# MainBoard_Box.net
KiCad netlist of a schematic drawn in Altium Designer
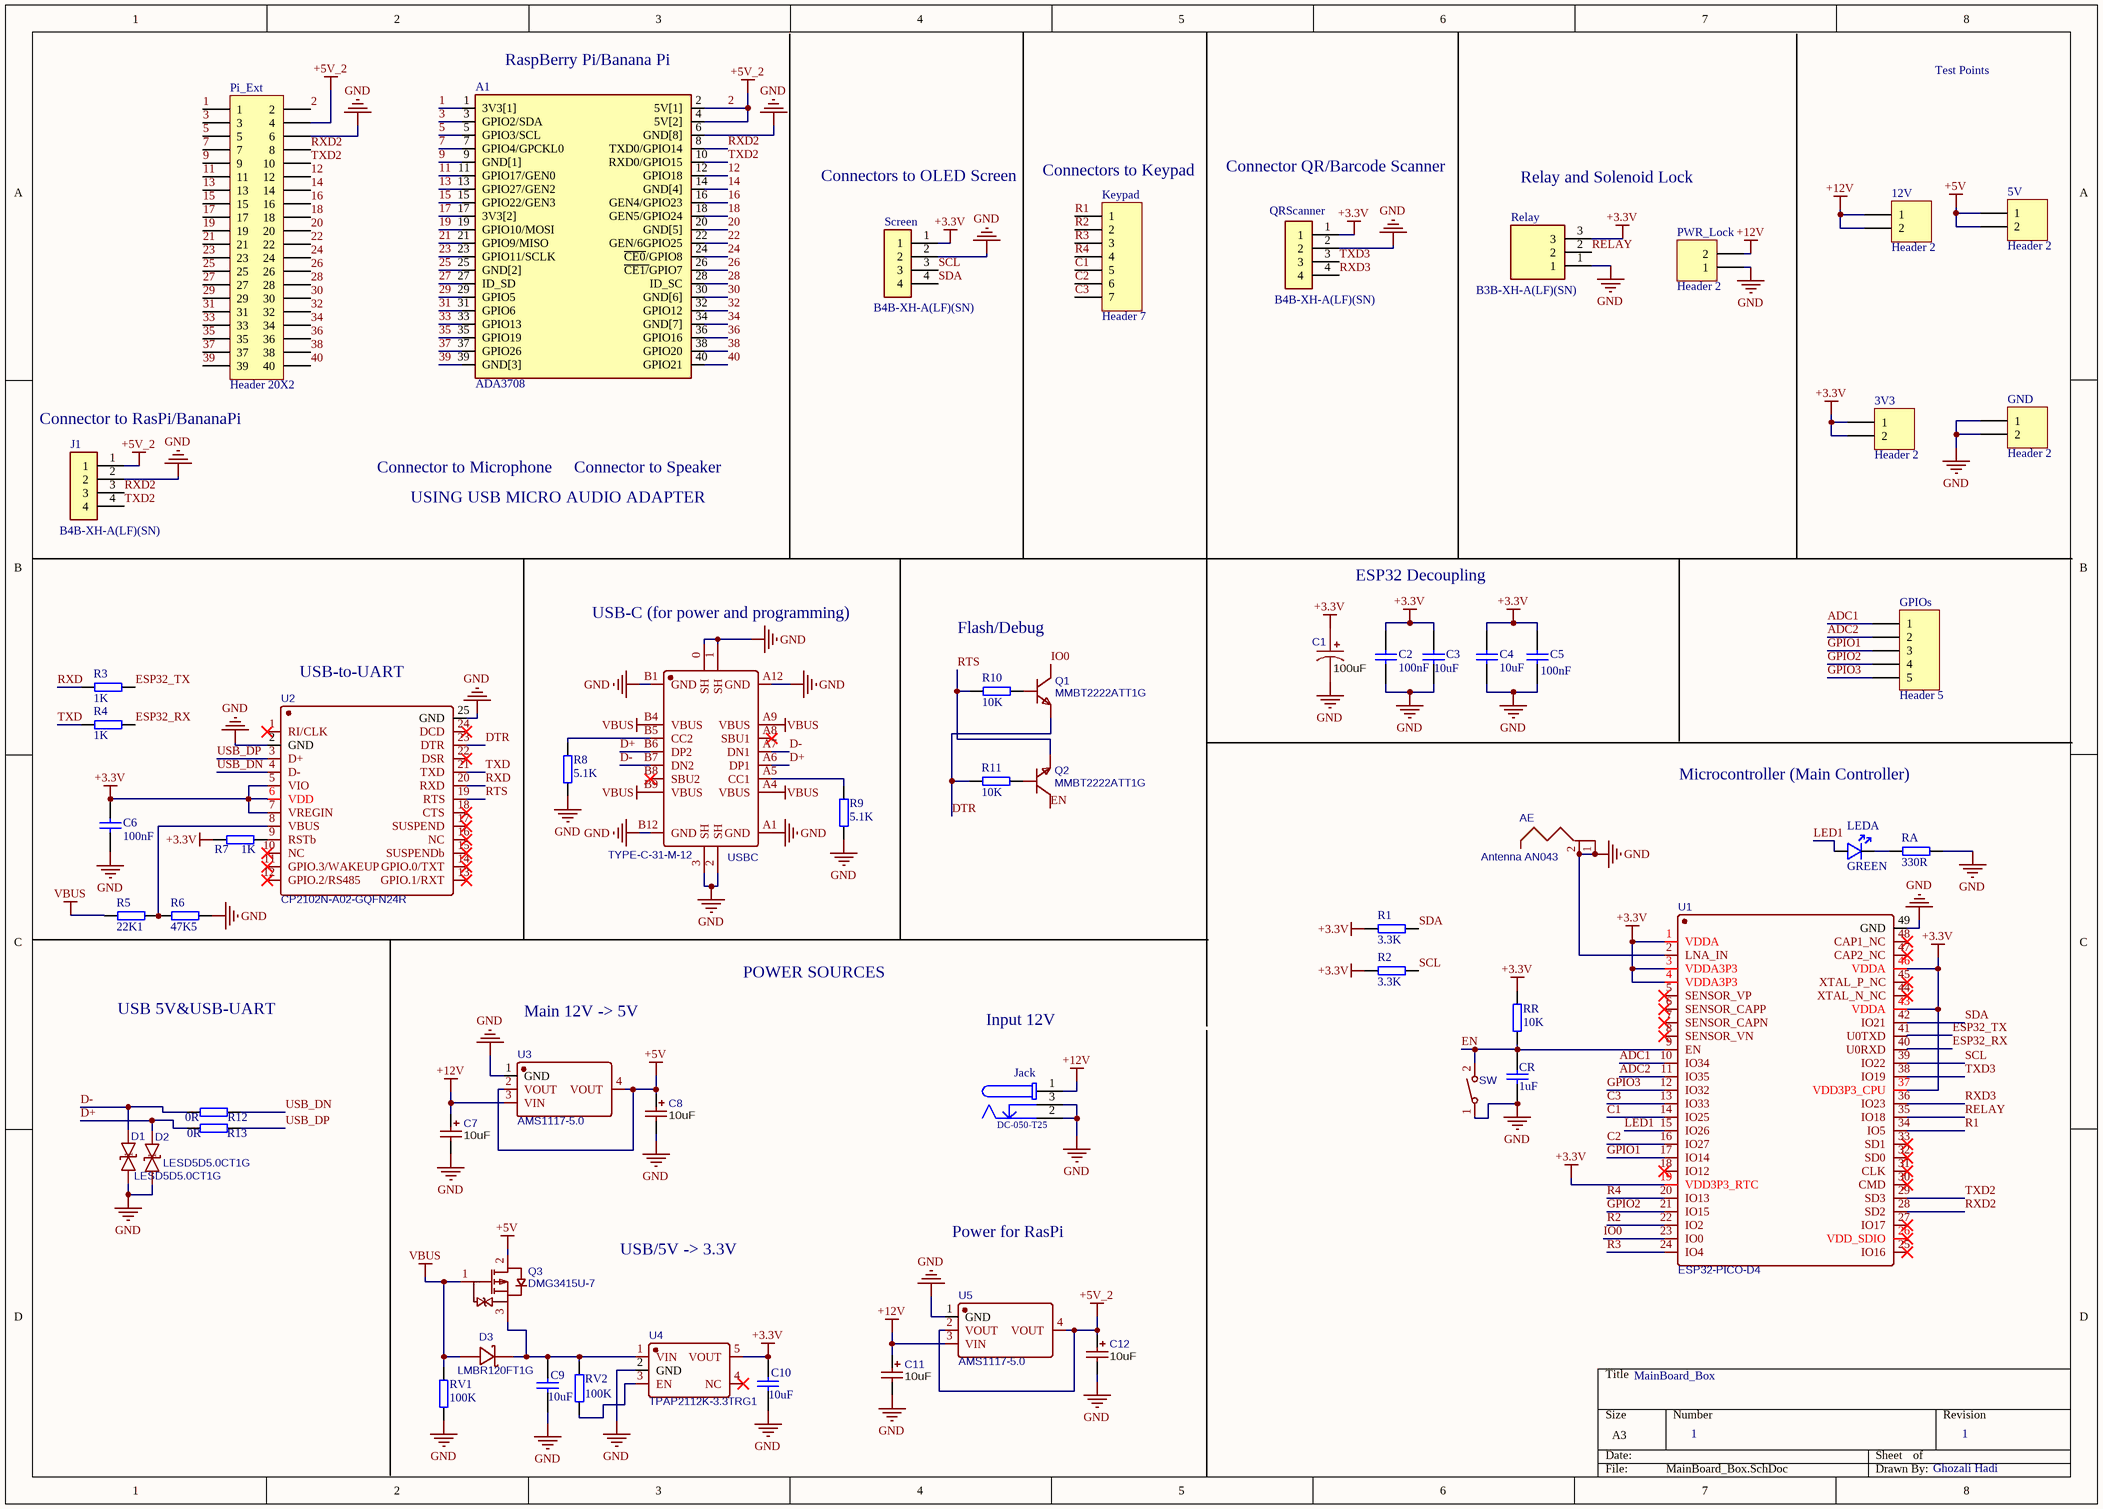
[diagram p0: MainBoard_Box.SchDoc]

(export (version "E")
  (design (tool "Eeschema 10.0.6"))
  (components
    (comp (ref "3V3")
      (value "Header 2")
      (footprint "HDR1X2")
      (description "Header, 2-Pin")
      (fields (field (name "PUBLISHER") "Altium Limited"))
      (libsource (lib "Miscellaneous Connectors") (part "Header 2"))
    )
    (comp (ref "5V")
      (value "Header 2")
      (footprint "HDR1X2")
      (description "Header, 2-Pin")
      (fields (field (name "PUBLISHER") "Altium Limited"))
      (libsource (lib "Miscellaneous Connectors") (part "Header 2"))
    )
    (comp (ref "12V")
      (value "Header 2")
      (footprint "HDR1X2")
      (description "Header, 2-Pin")
      (fields (field (name "PUBLISHER") "Altium Limited"))
      (libsource (lib "Miscellaneous Connectors") (part "Header 2"))
    )
    (comp (ref "A1")
      (value "ADA3708")
      (footprint "ADA3708_RPI-ZERO")
      (description "Raspberry Pi Zero WH (Zero W with Headers)")
      (libsource (lib "Box_Embedded") (part "ADA3708"))
    )
    (comp (ref "AE")
      (value "Antenna AN043")
      (footprint "AN043")
      (description "Small Size 2.4 GHz PCB antenna")
      (fields (field (name "MF") "Texas Instruments") (field (name "MP") "AN043"))
      (libsource (lib "ApolloLibrary") (part "Antenna AN043"))
    )
    (comp (ref "C1")
      (value "100uF")
      (footprint "CASE-C_6032")
      (description "100uF 10V -55℃~+125℃ 300mΩ@100kHz ±10% CASE-C_6032 Tantalum Capacitors")
      (fields (field (name "JLCPCB PART #") "C171664") (field (name "MF") "TORCH"))
      (libsource (lib "RiderDome") (part "Cap_100uF"))
    )
    (comp (ref "C2")
      (value "100nF")
      (footprint "CAP0402")
      (description "16V 100nF X7R ±10% 0402 Multilayer Ceramic Capacitors MLCC")
      (fields (field (name "MP") "CC0402KRX7R7BB104") (field (name "MF") "YAGEO"))
      (libsource (lib "electronpowered") (part "CAP"))
    )
    (comp (ref "C3")
      (value "10uF")
      (footprint "CAP0402")
      (description "6.3V 10uF X5R ±20% 0402 Multilayer Ceramic Capacitors MLCC")
      (fields (field (name "MP") "CL05A106MQ5NUNC") (field (name "MF") "SAMSUNG"))
      (libsource (lib "electronpowered") (part "CAP"))
    )
    (comp (ref "C4")
      (value "10uF")
      (footprint "CAP0402")
      (description "6.3V 10uF X5R ±20% 0402 Multilayer Ceramic Capacitors MLCC")
      (fields (field (name "MP") "CL05A106MQ5NUNC") (field (name "MF") "SAMSUNG"))
      (libsource (lib "electronpowered") (part "CAP"))
    )
    (comp (ref "C5")
      (value "100nF")
      (footprint "CAP0402")
      (description "16V 100nF X7R ±10% 0402 Multilayer Ceramic Capacitors MLCC")
      (fields (field (name "MP") "CC0402KRX7R7BB104") (field (name "MF") "YAGEO"))
      (libsource (lib "electronpowered") (part "CAP"))
    )
    (comp (ref "C6")
      (value "100nF")
      (footprint "CAP0402")
      (description "16V 100nF X7R ±10% 0402 Multilayer Ceramic Capacitors MLCC")
      (fields (field (name "MP") "CC0402KRX7R7BB104") (field (name "MF") "YAGEO"))
      (libsource (lib "electronpowered") (part "CAP"))
    )
    (comp (ref "C7")
      (value "10uF")
      (footprint "CAP-SMD_L3.2-W1.6-R-RD")
      (description "TANTALUM CAPACITORS 10UF 16V CASE-A_3216")
      (fields (field (name "LCSC PART #") "C7171") (field (name "MF") "AVX"))
      (libsource (lib "BuckleLibrary") (part "TAJA106K016RNJ"))
    )
    (comp (ref "C8")
      (value "10uF")
      (footprint "CAP-SMD_L3.2-W1.6-R-RD")
      (description "TANTALUM CAPACITORS 10UF 16V CASE-A_3216")
      (fields (field (name "LCSC PART #") "C7171") (field (name "MF") "AVX"))
      (libsource (lib "BuckleLibrary") (part "TAJA106K016RNJ"))
    )
    (comp (ref "C9")
      (value "10uF")
      (footprint "CAP0402")
      (description "6.3V 10uF X5R ±20% 0402 Multilayer Ceramic Capacitors MLCC")
      (fields (field (name "MP") "CL05A106MQ5NUNC") (field (name "MF") "SAMSUNG"))
      (libsource (lib "electronpowered") (part "CAP"))
    )
    (comp (ref "C10")
      (value "10uF")
      (footprint "CAP0402")
      (description "6.3V 10uF X5R ±20% 0402 Multilayer Ceramic Capacitors MLCC")
      (fields (field (name "MP") "CL05A106MQ5NUNC") (field (name "MF") "SAMSUNG"))
      (libsource (lib "electronpowered") (part "CAP"))
    )
    (comp (ref "C11")
      (value "10uF")
      (footprint "CAP-SMD_L3.2-W1.6-R-RD")
      (description "TANTALUM CAPACITORS 10UF 16V CASE-A_3216")
      (fields (field (name "LCSC PART #") "C7171") (field (name "MF") "AVX"))
      (libsource (lib "BuckleLibrary") (part "TAJA106K016RNJ"))
    )
    (comp (ref "C12")
      (value "10uF")
      (footprint "CAP-SMD_L3.2-W1.6-R-RD")
      (description "TANTALUM CAPACITORS 10UF 16V CASE-A_3216")
      (fields (field (name "LCSC PART #") "C7171") (field (name "MF") "AVX"))
      (libsource (lib "BuckleLibrary") (part "TAJA106K016RNJ"))
    )
    (comp (ref "CR")
      (value "1uF")
      (footprint "CAP0402")
      (description "MULTILAYER CERAMIC CAPACITORS MLCC - SMD/SMT 1UF 25V 0402")
      (fields
        (field (name "PART NUMBER") "CL05A105KA5NQNC")
        (field (name "MANUFACTURER") "Samsung Electro-Mechanics")
      )
      (libsource (lib "electronpowered") (part "CAP"))
    )
    (comp (ref "D1")
      (value "LESD5D5.0CT1G")
      (footprint "SOD-523_L1.2-W0.8-LS1.6-BI")
      (description "18.6V 9.4A (8/20us) 5V Bidirectional 5.6V SOD-523 ESD Protection Devices")
      (fields (field (name "LCSC PART #") "C383211") (field (name "MF") "Leshan Radio"))
      (libsource (lib "RiderDome") (part "LESD5D5.0CT1G"))
    )
    (comp (ref "D2")
      (value "LESD5D5.0CT1G")
      (footprint "SOD-523_L1.2-W0.8-LS1.6-BI")
      (description "18.6V 9.4A (8/20us) 5V Bidirectional 5.6V SOD-523 ESD Protection Devices")
      (fields (field (name "LCSC PART #") "C383211") (field (name "MF") "Leshan Radio"))
      (libsource (lib "RiderDome") (part "LESD5D5.0CT1G"))
    )
    (comp (ref "D3")
      (value "LMBR120FT1G")
      (footprint "SOD-123_L2.8-W1.8-LS3.7-RD")
      (description "20V 500mV@1A 1A SOD-123 Schottky Barrier Diodes (SBD)")
      (fields (field (name "MF") "LRC") (field (name "JLCPCB PART #") "C81143"))
      (libsource (lib "GameDev") (part "LMBR120FT1G"))
    )
    (comp (ref "GND")
      (value "Header 2")
      (footprint "HDR1X2")
      (description "Header, 2-Pin")
      (fields (field (name "PUBLISHER") "Altium Limited"))
      (libsource (lib "Miscellaneous Connectors") (part "Header 2"))
    )
    (comp (ref "GPIOs")
      (value "Header 5")
      (footprint "HDR1X5")
      (description "Header, 5-Pin")
      (fields (field (name "PUBLISHER") "Altium Limited"))
      (libsource (lib "AquaponicsLibrary") (part "Header 5"))
    )
    (comp (ref "J1")
      (value "B4B-XH-A(LF)(SN)")
      (footprint "JST_B4B-XH-A(LF)(SN)")
      (description "Connector Header Through Hole 4 position 0.098 _2.50mm_")
      (fields (field (name "MP") "B4B-XH-A_LF__SN_") (field (name "MF") "JST Sales"))
      (libsource (lib "AquaponicsLibrary") (part "B4B-XH-A(LF)(SN)"))
    )
    (comp (ref "Jack")
      (value "DC-050-T25")
      (footprint "694108106102")
      (description "3A 12V SMD AC/DC Power Connectors")
      (fields (field (name "MF") "SOFNG") (field (name "JLCPCB PART #") "C113716"))
      (libsource (lib "AquaponicsLibrary") (part "DC Jack SMD"))
    )
    (comp (ref "Keypad")
      (value "Header 7")
      (footprint "HDR1X7")
      (description "Header, 7-Pin")
      (fields (field (name "PUBLISHER") "Altium Limited"))
      (libsource (lib "Miscellaneous Connectors") (part "Header 7"))
    )
    (comp (ref "LEDA")
      (value "GREEN")
      (footprint "LED0603P")
      (description "LIGHT EMITTING DIODES (LED) GREEN 520~535NM 112~258MCD@20MA TOP VIEW 0603")
      (fields
        (field (name "PART NUMBER") "19-217/GHC-YR1S2/3T")
        (field (name "MANUFACTURER") "Everlight Elec")
      )
      (libsource (lib "electronpowered") (part "LED"))
    )
    (comp (ref "Pi_Ext")
      (value "Header 20X2")
      (footprint "HDR2X20")
      (description "Header, 20-Pin, Dual row")
      (fields (field (name "PUBLISHER") "Altium Limited"))
      (libsource (lib "Miscellaneous Connectors") (part "Header 20X2"))
    )
    (comp (ref "PWR_Lock")
      (value "Header 2")
      (footprint "HDR1X2")
      (description "Header, 2-Pin")
      (fields (field (name "PUBLISHER") "Altium Limited"))
      (libsource (lib "AquaponicsLibrary") (part "Header 2"))
    )
    (comp (ref "Q1")
      (value "MMBT2222ATT1G")
      (footprint "SC-75-3_L1.6-W0.8-P1.00-LS1.6-BR")
      (description "NPN 600mA 40V 150mW SC-75(SOT-523) Transistors (NPN/PNP)")
      (fields (field (name "MF") "ON Semiconductor") (field (name "LCSC PART #") "C94417"))
      (libsource (lib "EMV-Library") (part "MMBT2222ATT1G"))
    )
    (comp (ref "Q2")
      (value "MMBT2222ATT1G")
      (footprint "SC-75-3_L1.6-W0.8-P1.00-LS1.6-BR")
      (description "NPN 600mA 40V 150mW SC-75(SOT-523) Transistors (NPN/PNP)")
      (fields (field (name "MF") "ON Semiconductor") (field (name "LCSC PART #") "C94417"))
      (libsource (lib "EMV-Library") (part "MMBT2222ATT1G"))
    )
    (comp (ref "Q3")
      (value "DMG3415U-7")
      (footprint "SOT-23-3_L2.9-W1.6-P1.90-LS2.8-BR-CW")
      (description "SOT-23-3 MOSFETs")
      (fields (field (name "JLCPCB PART #") "C709946") (field (name "MF") "VBsemi Elec"))
      (libsource (lib "GameDev") (part "DMG3415U-7"))
    )
    (comp (ref "QRScanner")
      (value "B4B-XH-A(LF)(SN)")
      (footprint "JST_B4B-XH-A(LF)(SN)")
      (description "Connector Header Through Hole 4 position 0.098 _2.50mm_")
      (fields (field (name "MP") "B4B-XH-A_LF__SN_") (field (name "MF") "JST Sales"))
      (libsource (lib "AquaponicsLibrary") (part "B4B-XH-A(LF)(SN)"))
    )
    (comp (ref "R1")
      (value "3.3K")
      (footprint "RES0402")
      (description "62.5mW Thick Film Resistors 50V ±100ppm/℃ ±1% -55℃~+155℃ 3.3kΩ 0402 Chip Resistor - Surface Mount")
      (fields (field (name "MP") "RC0402FR-073K3L") (field (name "MF") "YAGEO"))
      (libsource (lib "electronpowered") (part "RES"))
    )
    (comp (ref "R2")
      (value "3.3K")
      (footprint "RES0402")
      (description "62.5mW Thick Film Resistors 50V ±100ppm/℃ ±1% -55℃~+155℃ 3.3kΩ 0402 Chip Resistor - Surface Mount")
      (fields (field (name "MP") "RC0402FR-073K3L") (field (name "MF") "YAGEO"))
      (libsource (lib "electronpowered") (part "RES"))
    )
    (comp (ref "R3")
      (value "1K")
      (footprint "RES0402")
      (description "±1% 1/16W Thick Film Resistors 50V ±100ppm/℃ -55℃~+155℃ 1kΩ 0402 Chip Resistor")
      (fields (field (name "MP") "0402WGF1001TCE") (field (name "MF") "UNI-ROYAL(Uniroyal Elec)"))
      (libsource (lib "electronpowered") (part "RES"))
    )
    (comp (ref "R4")
      (value "1K")
      (footprint "RES0402")
      (description "±1% 1/16W Thick Film Resistors 50V ±100ppm/℃ -55℃~+155℃ 1kΩ 0402 Chip Resistor")
      (fields (field (name "MP") "0402WGF1001TCE") (field (name "MF") "UNI-ROYAL(Uniroyal Elec)"))
      (libsource (lib "electronpowered") (part "RES"))
    )
    (comp (ref "R5")
      (value "22K1")
      (footprint "RES0402")
      (description "±1% 1/16W Thick Film Resistors 50V ±100ppm/℃ -55℃~+155℃ 22.1kΩ 0402 Chip Resistor - Surface Mount")
      (fields (field (name "MP") "0402WGF2212TCE") (field (name "MF") "UNI-ROYAL(Uniroyal Elec)"))
      (libsource (lib "electronpowered") (part "RES"))
    )
    (comp (ref "R6")
      (value "47K5")
      (footprint "RES0402")
      (description "±1% 1/16W Thick Film Resistors 50V ±100ppm/℃ -55℃~+155℃ 47.5kΩ 0402 Chip Resistor - Surface Mount")
      (fields (field (name "MP") "0402WGF4752TCE") (field (name "MF") "UNI-ROYAL(Uniroyal Elec)"))
      (libsource (lib "electronpowered") (part "RES"))
    )
    (comp (ref "R7")
      (value "1K")
      (footprint "RES0402")
      (description "±1% 1/16W Thick Film Resistors 50V ±100ppm/℃ -55℃~+155℃ 1kΩ 0402 Chip Resistor")
      (fields (field (name "MP") "0402WGF1001TCE") (field (name "MF") "UNI-ROYAL(Uniroyal Elec)"))
      (libsource (lib "electronpowered") (part "RES"))
    )
    (comp (ref "R8")
      (value "5.1K")
      (footprint "RES0402")
      (description "5.1kΩ 0402 1/16W 50V ±5% ±100ppm/℃  Chip Resistor - Surface Mount")
      (fields (field (name "MP") "RC0402JR-075K1L") (field (name "MF") "YAGEO"))
      (libsource (lib "electronpowered") (part "RES"))
    )
    (comp (ref "R9")
      (value "5.1K")
      (footprint "RES0402")
      (description "5.1kΩ 0402 1/16W 50V ±5% ±100ppm/℃  Chip Resistor - Surface Mount")
      (fields (field (name "MP") "RC0402JR-075K1L") (field (name "MF") "YAGEO"))
      (libsource (lib "electronpowered") (part "RES"))
    )
    (comp (ref "R10")
      (value "10K")
      (footprint "RES0402")
      (description "CHIP RESISTOR - SURFACE MOUNT 10KOHMS ±1% 1/16W 0402")
      (fields (field (name "MP") "0402WGF1002TCE") (field (name "MF") "Uniroyal Elec"))
      (libsource (lib "electronpowered") (part "RES"))
    )
    (comp (ref "R11")
      (value "10K")
      (footprint "RES0402")
      (description "CHIP RESISTOR - SURFACE MOUNT 10KOHMS ±1% 1/16W 0402")
      (fields (field (name "MP") "0402WGF1002TCE") (field (name "MF") "Uniroyal Elec"))
      (libsource (lib "electronpowered") (part "RES"))
    )
    (comp (ref "R12")
      (value "0R")
      (footprint "RES0402")
      (description "1/16W ±1% 0Ω 0402 Chip Resistor")
      (fields (field (name "MP") "RC0402FR-070RL") (field (name "MF") "YAGEO"))
      (libsource (lib "electronpowered") (part "RES"))
    )
    (comp (ref "R13")
      (value "0R")
      (footprint "RES0402")
      (description "1/16W ±1% 0Ω 0402 Chip Resistor")
      (fields (field (name "MP") "RC0402FR-070RL") (field (name "MF") "YAGEO"))
      (libsource (lib "electronpowered") (part "RES"))
    )
    (comp (ref "RA")
      (value "330R")
      (footprint "RES0402")
      (description "CHIP RESISTOR - SURFACE MOUNT 330OHMS ±1% 1/16W 0402")
      (fields (field (name "PART NUMBER") "0402WGF3300TCE") (field (name "MANUFACTURER") "Uniroyal Elec"))
      (libsource (lib "electronpowered") (part "RES"))
    )
    (comp (ref "Relay")
      (value "B3B-XH-A(LF)(SN)")
      (footprint "JST_B3B-XH-A(LF)(SN)")
      (description "Connector Header Through Hole 3 position 0.098 (2.50mm)")
      (fields (field (name "MF") "JST Sales"))
      (libsource (lib "AquaponicsLibrary") (part "B3B-XH-A(LF)(SN)"))
    )
    (comp (ref "RR")
      (value "10K")
      (footprint "RES0402")
      (description "CHIP RESISTOR - SURFACE MOUNT 10KOHMS ±1% 1/16W 0402")
      (fields (field (name "MP") "0402WGF1002TCE") (field (name "MF") "Uniroyal Elec"))
      (libsource (lib "electronpowered") (part "RES"))
    )
    (comp (ref "RV1")
      (value "100K")
      (footprint "RES0402")
      (description "62.5mW Thick Film Resistors 50V ±100ppm/℃ ±1% -55℃~+155℃ 100kΩ 0402 Chip Resistor - Surface Mount")
      (fields (field (name "MP") "RC0402FR-07100KL") (field (name "MF") "YAGEO"))
      (libsource (lib "electronpowered") (part "RES"))
    )
    (comp (ref "RV2")
      (value "100K")
      (footprint "RES0402")
      (description "62.5mW Thick Film Resistors 50V ±100ppm/℃ ±1% -55℃~+155℃ 100kΩ 0402 Chip Resistor - Surface Mount")
      (fields (field (name "MP") "RC0402FR-07100KL") (field (name "MF") "YAGEO"))
      (libsource (lib "electronpowered") (part "RES"))
    )
    (comp (ref "Screen")
      (value "B4B-XH-A(LF)(SN)")
      (footprint "JST_B4B-XH-A(LF)(SN)")
      (description "Connector Header Through Hole 4 position 0.098 _2.50mm_")
      (fields (field (name "MP") "B4B-XH-A_LF__SN_") (field (name "MF") "JST Sales"))
      (libsource (lib "AquaponicsLibrary") (part "B4B-XH-A(LF)(SN)"))
    )
    (comp (ref "SW")
      (value "TS-1092S-B3D2-G")
      (footprint "SW-SMD_L6.1-W3.6-LS7.9")
      (fields (field (name "JLCPCB PART #") "C520860") (field (name "MF") "Yuandi"))
      (libsource (lib "GameDev") (part "TS-1092S-B3D2-G"))
    )
    (comp (ref "U1")
      (value "ESP32-PICO-D4")
      (footprint "QFN-48_L7.0-W7.0-P0.50-BL-EP5.4")
      (description "QFN-48_7x7x05P RF Transceiver ICs")
      (fields (field (name "LCSC PART #") "C193707") (field (name "MF") "Espressif Systems"))
      (libsource (lib "RiderDome") (part "ESP32-PICO-D4"))
    )
    (comp (ref "U2")
      (value "CP2102N-A02-GQFN24R")
      (footprint "QFN-24_L4.0-W4.0-P0.50-TL-EP2.6")
      (description "QFN-24_4x4x05P USB ICs")
      (fields (field (name "LCSC PART #") "C969151") (field (name "MF") "SILICON LABS"))
      (libsource (lib "RiderDome") (part "CP2102N-A02-GQFN24R"))
    )
    (comp (ref "U3")
      (value "AMS1117-5.0")
      (footprint "SOT-223_L6.5-W3.5-P2.30-LS7.0-BR")
      (description "68dB@(120Hz) 1A 1.3V@(1A) Fixed 5V~5V Positive 1 15V SOT-223 Linear Voltage Regulators (LDO)")
      (fields (field (name "MF") "AMS") (field (name "JLCPCB PART #") "C6187"))
      (libsource (lib "Box_Embedded") (part "AMS1117-5.0"))
    )
    (comp (ref "U4")
      (value "TPAP2112K-3.3TRG1")
      (footprint "SOT-23-5_L2.9-W1.6-P0.95-LS2.8-BR")
      (description "SOT-23-5 Linear Voltage Regulators (LDO)")
      (fields (field (name "JLCPCB PART #") "C3021085") (field (name "MF") "TECH PUBLIC"))
      (libsource (lib "GameDev") (part "TPAP2112K-3.3TRG1"))
    )
    (comp (ref "U5")
      (value "AMS1117-5.0")
      (footprint "SOT-223_L6.5-W3.5-P2.30-LS7.0-BR")
      (description "68dB@(120Hz) 1A 1.3V@(1A) Fixed 5V~5V Positive 1 15V SOT-223 Linear Voltage Regulators (LDO)")
      (fields (field (name "MF") "AMS") (field (name "JLCPCB PART #") "C6187"))
      (libsource (lib "Box_Embedded") (part "AMS1117-5.0"))
    )
    (comp (ref "USBC")
      (value "TYPE-C-31-M-12")
      (footprint "USB-C_SMD-TYPE-C-31-M-12")
      (description "5A 1 16 Female Type-C SMD USB Connectors")
      (fields (field (name "JLCPCB PART #") "C165948") (field (name "MF") "Korean Hroparts Elec"))
      (libsource (lib "GameDev") (part "TYPE-C-31-M-12"))
    )
  )
  (nets
    (net (code "1") (name "+3.3V") (class "Default")
      (node (ref "3V3") (pin "1") (pinfunction "1_1") (pintype "passive"))
      (node (ref "3V3") (pin "2") (pinfunction "2_2") (pintype "passive"))
      (node (ref "C1") (pin "1") (pinfunction "1_1") (pintype "passive"))
      (node (ref "C10") (pin "2") (pinfunction "2_2") (pintype "passive"))
      (node (ref "C2") (pin "2") (pinfunction "2_2") (pintype "passive"))
      (node (ref "C3") (pin "2") (pinfunction "2_2") (pintype "passive"))
      (node (ref "C4") (pin "2") (pinfunction "2_2") (pintype "passive"))
      (node (ref "C5") (pin "2") (pinfunction "2_2") (pintype "passive"))
      (node (ref "C6") (pin "2") (pinfunction "2_2") (pintype "passive"))
      (node (ref "QRScanner") (pin "1") (pinfunction "1_1") (pintype "passive"))
      (node (ref "R1") (pin "1") (pinfunction "1_1") (pintype "passive"))
      (node (ref "R2") (pin "1") (pinfunction "1_1") (pintype "passive"))
      (node (ref "R7") (pin "2") (pinfunction "2_2") (pintype "passive"))
      (node (ref "RR") (pin "1") (pinfunction "1_1") (pintype "passive"))
      (node (ref "Relay") (pin "3") (pinfunction "3_3") (pintype "passive"))
      (node (ref "Screen") (pin "1") (pinfunction "1_1") (pintype "passive"))
      (node (ref "U1") (pin "1") (pinfunction "VDDA_1") (pintype "passive"))
      (node (ref "U1") (pin "19") (pinfunction "VDD3P3_RTC_19") (pintype "passive"))
      (node (ref "U1") (pin "3") (pinfunction "VDDA3P3_3") (pintype "passive"))
      (node (ref "U1") (pin "37") (pinfunction "VDD3P3_CPU_37") (pintype "passive"))
      (node (ref "U1") (pin "4") (pinfunction "VDDA3P3_4") (pintype "passive"))
      (node (ref "U1") (pin "43") (pinfunction "VDDA_43") (pintype "passive"))
      (node (ref "U1") (pin "46") (pinfunction "VDDA_46") (pintype "passive"))
      (node (ref "U2") (pin "5") (pinfunction "VIO_5") (pintype "passive"))
      (node (ref "U2") (pin "6") (pinfunction "VDD_6") (pintype "passive"))
      (node (ref "U2") (pin "7") (pinfunction "VREGIN_7") (pintype "passive"))
      (node (ref "U4") (pin "5") (pinfunction "VOUT_5") (pintype "passive"))
    )
    (net (code "2") (name "+5V") (class "Default")
      (node (ref "5V") (pin "1") (pinfunction "1_1") (pintype "passive"))
      (node (ref "5V") (pin "2") (pinfunction "2_2") (pintype "passive"))
      (node (ref "C8") (pin "1") (pinfunction "1_1") (pintype "passive"))
      (node (ref "Q3") (pin "2") (pinfunction "D_2") (pintype "passive"))
      (node (ref "U3") (pin "2") (pinfunction "VOUT_2") (pintype "passive"))
      (node (ref "U3") (pin "4") (pinfunction "VOUT_4") (pintype "passive"))
    )
    (net (code "3") (name "+5V_2") (class "Default")
      (node (ref "A1") (pin "2") (pinfunction "5V[1]_2") (pintype "power_in"))
      (node (ref "A1") (pin "4") (pinfunction "5V[2]_4") (pintype "power_in"))
      (node (ref "C12") (pin "1") (pinfunction "1_1") (pintype "passive"))
      (node (ref "J1") (pin "1") (pinfunction "1_1") (pintype "passive"))
      (node (ref "Pi_Ext") (pin "2") (pinfunction "2_2") (pintype "passive"))
      (node (ref "Pi_Ext") (pin "4") (pinfunction "4_4") (pintype "passive"))
      (node (ref "U5") (pin "2") (pinfunction "VOUT_2") (pintype "passive"))
      (node (ref "U5") (pin "4") (pinfunction "VOUT_4") (pintype "passive"))
    )
    (net (code "4") (name "+12V") (class "Default")
      (node (ref "12V") (pin "1") (pinfunction "1_1") (pintype "passive"))
      (node (ref "12V") (pin "2") (pinfunction "2_2") (pintype "passive"))
      (node (ref "C11") (pin "1") (pinfunction "1_1") (pintype "passive"))
      (node (ref "C7") (pin "1") (pinfunction "1_1") (pintype "passive"))
      (node (ref "Jack") (pin "1") (pinfunction "1_1") (pintype "passive"))
      (node (ref "PWR_Lock") (pin "2") (pinfunction "2_2") (pintype "passive"))
      (node (ref "U3") (pin "3") (pinfunction "VIN_3") (pintype "passive"))
      (node (ref "U5") (pin "3") (pinfunction "VIN_3") (pintype "passive"))
    )
    (net (code "5") (name "/1") (class "Default")
      (node (ref "A1") (pin "1") (pinfunction "3V3[1]_1") (pintype "power_in"))
      (node (ref "Pi_Ext") (pin "1") (pinfunction "1_1") (pintype "passive"))
    )
    (net (code "6") (name "/3") (class "Default")
      (node (ref "A1") (pin "3") (pinfunction "GPIO2/SDA_3") (pintype "bidirectional"))
      (node (ref "Pi_Ext") (pin "3") (pinfunction "3_3") (pintype "passive"))
    )
    (net (code "7") (name "/5") (class "Default")
      (node (ref "A1") (pin "5") (pinfunction "GPIO3/SCL_5") (pintype "bidirectional"))
      (node (ref "Pi_Ext") (pin "5") (pinfunction "5_5") (pintype "passive"))
    )
    (net (code "8") (name "/7") (class "Default")
      (node (ref "A1") (pin "7") (pinfunction "GPIO4/GPCKL0_7") (pintype "bidirectional"))
      (node (ref "Pi_Ext") (pin "7") (pinfunction "7_7") (pintype "passive"))
    )
    (net (code "9") (name "/9") (class "Default")
      (node (ref "A1") (pin "9") (pinfunction "GND[1]_9") (pintype "power_in"))
      (node (ref "Pi_Ext") (pin "9") (pinfunction "9_9") (pintype "passive"))
    )
    (net (code "10") (name "/11") (class "Default")
      (node (ref "A1") (pin "11") (pinfunction "GPIO17/GEN0_11") (pintype "bidirectional"))
      (node (ref "Pi_Ext") (pin "11") (pinfunction "11_11") (pintype "passive"))
    )
    (net (code "11") (name "/12") (class "Default")
      (node (ref "A1") (pin "12") (pinfunction "GPIO18_12") (pintype "bidirectional"))
      (node (ref "Pi_Ext") (pin "12") (pinfunction "12_12") (pintype "passive"))
    )
    (net (code "12") (name "/13") (class "Default")
      (node (ref "A1") (pin "13") (pinfunction "GPIO27/GEN2_13") (pintype "bidirectional"))
      (node (ref "Pi_Ext") (pin "13") (pinfunction "13_13") (pintype "passive"))
    )
    (net (code "13") (name "/14") (class "Default")
      (node (ref "A1") (pin "14") (pinfunction "GND[4]_14") (pintype "power_in"))
      (node (ref "Pi_Ext") (pin "14") (pinfunction "14_14") (pintype "passive"))
    )
    (net (code "14") (name "/15") (class "Default")
      (node (ref "A1") (pin "15") (pinfunction "GPIO22/GEN3_15") (pintype "bidirectional"))
      (node (ref "Pi_Ext") (pin "15") (pinfunction "15_15") (pintype "passive"))
    )
    (net (code "15") (name "/16") (class "Default")
      (node (ref "A1") (pin "16") (pinfunction "GEN4/GPIO23_16") (pintype "bidirectional"))
      (node (ref "Pi_Ext") (pin "16") (pinfunction "16_16") (pintype "passive"))
    )
    (net (code "16") (name "/17") (class "Default")
      (node (ref "A1") (pin "17") (pinfunction "3V3[2]_17") (pintype "power_in"))
      (node (ref "Pi_Ext") (pin "17") (pinfunction "17_17") (pintype "passive"))
    )
    (net (code "17") (name "/18") (class "Default")
      (node (ref "A1") (pin "18") (pinfunction "GEN5/GPIO24_18") (pintype "bidirectional"))
      (node (ref "Pi_Ext") (pin "18") (pinfunction "18_18") (pintype "passive"))
    )
    (net (code "18") (name "/19") (class "Default")
      (node (ref "A1") (pin "19") (pinfunction "GPIO10/MOSI_19") (pintype "bidirectional"))
      (node (ref "Pi_Ext") (pin "19") (pinfunction "19_19") (pintype "passive"))
    )
    (net (code "19") (name "/20") (class "Default")
      (node (ref "A1") (pin "20") (pinfunction "GND[5]_20") (pintype "power_in"))
      (node (ref "Pi_Ext") (pin "20") (pinfunction "20_20") (pintype "passive"))
    )
    (net (code "20") (name "/21") (class "Default")
      (node (ref "A1") (pin "21") (pinfunction "GPIO9/MISO_21") (pintype "bidirectional"))
      (node (ref "Pi_Ext") (pin "21") (pinfunction "21_21") (pintype "passive"))
    )
    (net (code "21") (name "/22") (class "Default")
      (node (ref "A1") (pin "22") (pinfunction "GEN/6GPIO25_22") (pintype "bidirectional"))
      (node (ref "Pi_Ext") (pin "22") (pinfunction "22_22") (pintype "passive"))
    )
    (net (code "22") (name "/23") (class "Default")
      (node (ref "A1") (pin "23") (pinfunction "GPIO11/SCLK_23") (pintype "bidirectional"))
      (node (ref "Pi_Ext") (pin "23") (pinfunction "23_23") (pintype "passive"))
    )
    (net (code "23") (name "/24") (class "Default")
      (node (ref "A1") (pin "24") (pinfunction "~{CE0}/GPIO8_24") (pintype "bidirectional"))
      (node (ref "Pi_Ext") (pin "24") (pinfunction "24_24") (pintype "passive"))
    )
    (net (code "24") (name "/25") (class "Default")
      (node (ref "A1") (pin "25") (pinfunction "GND[2]_25") (pintype "power_in"))
      (node (ref "Pi_Ext") (pin "25") (pinfunction "25_25") (pintype "passive"))
    )
    (net (code "25") (name "/26") (class "Default")
      (node (ref "A1") (pin "26") (pinfunction "~{CE1/}GPIO7_26") (pintype "bidirectional"))
      (node (ref "Pi_Ext") (pin "26") (pinfunction "26_26") (pintype "passive"))
    )
    (net (code "26") (name "/27") (class "Default")
      (node (ref "A1") (pin "27") (pinfunction "ID_SD_27") (pintype "bidirectional"))
      (node (ref "Pi_Ext") (pin "27") (pinfunction "27_27") (pintype "passive"))
    )
    (net (code "27") (name "/28") (class "Default")
      (node (ref "A1") (pin "28") (pinfunction "ID_SC_28") (pintype "bidirectional"))
      (node (ref "Pi_Ext") (pin "28") (pinfunction "28_28") (pintype "passive"))
    )
    (net (code "28") (name "/29") (class "Default")
      (node (ref "A1") (pin "29") (pinfunction "GPIO5_29") (pintype "bidirectional"))
      (node (ref "Pi_Ext") (pin "29") (pinfunction "29_29") (pintype "passive"))
    )
    (net (code "29") (name "/30") (class "Default")
      (node (ref "A1") (pin "30") (pinfunction "GND[6]_30") (pintype "power_in"))
      (node (ref "Pi_Ext") (pin "30") (pinfunction "30_30") (pintype "passive"))
    )
    (net (code "30") (name "/31") (class "Default")
      (node (ref "A1") (pin "31") (pinfunction "GPIO6_31") (pintype "bidirectional"))
      (node (ref "Pi_Ext") (pin "31") (pinfunction "31_31") (pintype "passive"))
    )
    (net (code "31") (name "/32") (class "Default")
      (node (ref "A1") (pin "32") (pinfunction "GPIO12_32") (pintype "bidirectional"))
      (node (ref "Pi_Ext") (pin "32") (pinfunction "32_32") (pintype "passive"))
    )
    (net (code "32") (name "/33") (class "Default")
      (node (ref "A1") (pin "33") (pinfunction "GPIO13_33") (pintype "bidirectional"))
      (node (ref "Pi_Ext") (pin "33") (pinfunction "33_33") (pintype "passive"))
    )
    (net (code "33") (name "/34") (class "Default")
      (node (ref "A1") (pin "34") (pinfunction "GND[7]_34") (pintype "power_in"))
      (node (ref "Pi_Ext") (pin "34") (pinfunction "34_34") (pintype "passive"))
    )
    (net (code "34") (name "/35") (class "Default")
      (node (ref "A1") (pin "35") (pinfunction "GPIO19_35") (pintype "bidirectional"))
      (node (ref "Pi_Ext") (pin "35") (pinfunction "35_35") (pintype "passive"))
    )
    (net (code "35") (name "/36") (class "Default")
      (node (ref "A1") (pin "36") (pinfunction "GPIO16_36") (pintype "bidirectional"))
      (node (ref "Pi_Ext") (pin "36") (pinfunction "36_36") (pintype "passive"))
    )
    (net (code "36") (name "/37") (class "Default")
      (node (ref "A1") (pin "37") (pinfunction "GPIO26_37") (pintype "bidirectional"))
      (node (ref "Pi_Ext") (pin "37") (pinfunction "37_37") (pintype "passive"))
    )
    (net (code "37") (name "/38") (class "Default")
      (node (ref "A1") (pin "38") (pinfunction "GPIO20_38") (pintype "bidirectional"))
      (node (ref "Pi_Ext") (pin "38") (pinfunction "38_38") (pintype "passive"))
    )
    (net (code "38") (name "/39") (class "Default")
      (node (ref "A1") (pin "39") (pinfunction "GND[3]_39") (pintype "power_in"))
      (node (ref "Pi_Ext") (pin "39") (pinfunction "39_39") (pintype "passive"))
    )
    (net (code "39") (name "/40") (class "Default")
      (node (ref "A1") (pin "40") (pinfunction "GPIO21_40") (pintype "bidirectional"))
      (node (ref "Pi_Ext") (pin "40") (pinfunction "40_40") (pintype "passive"))
    )
    (net (code "40") (name "/ADC1") (class "Default")
      (node (ref "GPIOs") (pin "1") (pinfunction "1_1") (pintype "passive"))
      (node (ref "U1") (pin "10") (pinfunction "IO34_10") (pintype "passive"))
    )
    (net (code "41") (name "/ADC2") (class "Default")
      (node (ref "GPIOs") (pin "2") (pinfunction "2_2") (pintype "passive"))
      (node (ref "U1") (pin "11") (pinfunction "IO35_11") (pintype "passive"))
    )
    (net (code "42") (name "/C1") (class "Default")
      (node (ref "Keypad") (pin "5") (pinfunction "5_5") (pintype "passive"))
      (node (ref "U1") (pin "14") (pinfunction "IO25_14") (pintype "passive"))
    )
    (net (code "43") (name "/C2") (class "Default")
      (node (ref "Keypad") (pin "6") (pinfunction "6_6") (pintype "passive"))
      (node (ref "U1") (pin "16") (pinfunction "IO27_16") (pintype "passive"))
    )
    (net (code "44") (name "/C3") (class "Default")
      (node (ref "Keypad") (pin "7") (pinfunction "7_7") (pintype "passive"))
      (node (ref "U1") (pin "13") (pinfunction "IO33_13") (pintype "passive"))
    )
    (net (code "45") (name "/D+") (class "Default")
      (node (ref "D2") (pin "1") (pinfunction "1_1") (pintype "passive"))
      (node (ref "R13") (pin "2") (pinfunction "2_2") (pintype "passive"))
      (node (ref "USBC") (pin "A6") (pinfunction "DP1_A6") (pintype "passive"))
      (node (ref "USBC") (pin "B6") (pinfunction "DP2_B6") (pintype "passive"))
    )
    (net (code "46") (name "/D-") (class "Default")
      (node (ref "D1") (pin "1") (pinfunction "1_1") (pintype "passive"))
      (node (ref "R12") (pin "2") (pinfunction "2_2") (pintype "passive"))
      (node (ref "USBC") (pin "A7") (pinfunction "DN1_A7") (pintype "passive"))
      (node (ref "USBC") (pin "B7") (pinfunction "DN2_B7") (pintype "passive"))
    )
    (net (code "47") (name "/DTR") (class "Default")
      (node (ref "Q1") (pin "2") (pinfunction "E_2") (pintype "passive"))
      (node (ref "R11") (pin "1") (pinfunction "1_1") (pintype "passive"))
      (node (ref "U2") (pin "23") (pinfunction "DTR_23") (pintype "passive"))
    )
    (net (code "48") (name "/EN") (class "Default")
      (node (ref "CR") (pin "2") (pinfunction "2_2") (pintype "passive"))
      (node (ref "Q2") (pin "3") (pinfunction "C_3") (pintype "passive"))
      (node (ref "RR") (pin "2") (pinfunction "2_2") (pintype "passive"))
      (node (ref "SW") (pin "2") (pinfunction "2_2") (pintype "passive"))
      (node (ref "U1") (pin "9") (pinfunction "EN_9") (pintype "passive"))
    )
    (net (code "49") (name "/ESP32_RX") (class "Default")
      (node (ref "R4") (pin "1") (pinfunction "1_1") (pintype "passive"))
      (node (ref "U1") (pin "40") (pinfunction "U0RXD_40") (pintype "passive"))
    )
    (net (code "50") (name "/ESP32_TX") (class "Default")
      (node (ref "R3") (pin "1") (pinfunction "1_1") (pintype "passive"))
      (node (ref "U1") (pin "41") (pinfunction "U0TXD_41") (pintype "passive"))
    )
    (net (code "51") (name "/GPIO1") (class "Default")
      (node (ref "GPIOs") (pin "3") (pinfunction "3_3") (pintype "passive"))
      (node (ref "U1") (pin "17") (pinfunction "IO14_17") (pintype "passive"))
    )
    (net (code "52") (name "/GPIO2") (class "Default")
      (node (ref "GPIOs") (pin "4") (pinfunction "4_4") (pintype "passive"))
      (node (ref "U1") (pin "21") (pinfunction "IO15_21") (pintype "passive"))
    )
    (net (code "53") (name "/GPIO3") (class "Default")
      (node (ref "GPIOs") (pin "5") (pinfunction "5_5") (pintype "passive"))
      (node (ref "U1") (pin "12") (pinfunction "IO32_12") (pintype "passive"))
    )
    (net (code "54") (name "/IO0") (class "Default")
      (node (ref "Q1") (pin "3") (pinfunction "C_3") (pintype "passive"))
      (node (ref "U1") (pin "23") (pinfunction "IO0_23") (pintype "passive"))
    )
    (net (code "55") (name "/LED1") (class "Default")
      (node (ref "LEDA") (pin "1") (pinfunction "1_1") (pintype "passive"))
      (node (ref "U1") (pin "15") (pinfunction "IO26_15") (pintype "passive"))
    )
    (net (code "56") (name "/R1") (class "Default")
      (node (ref "Keypad") (pin "1") (pinfunction "1_1") (pintype "passive"))
      (node (ref "U1") (pin "34") (pinfunction "IO5_34") (pintype "passive"))
    )
    (net (code "57") (name "/R2") (class "Default")
      (node (ref "Keypad") (pin "2") (pinfunction "2_2") (pintype "passive"))
      (node (ref "U1") (pin "22") (pinfunction "IO2_22") (pintype "passive"))
    )
    (net (code "58") (name "/R3") (class "Default")
      (node (ref "Keypad") (pin "3") (pinfunction "3_3") (pintype "passive"))
      (node (ref "U1") (pin "24") (pinfunction "IO4_24") (pintype "passive"))
    )
    (net (code "59") (name "/R4") (class "Default")
      (node (ref "Keypad") (pin "4") (pinfunction "4_4") (pintype "passive"))
      (node (ref "U1") (pin "20") (pinfunction "IO13_20") (pintype "passive"))
    )
    (net (code "60") (name "/RELAY") (class "Default")
      (node (ref "Relay") (pin "2") (pinfunction "2_2") (pintype "passive"))
      (node (ref "U1") (pin "35") (pinfunction "IO18_35") (pintype "passive"))
    )
    (net (code "61") (name "/RTS") (class "Default")
      (node (ref "Q2") (pin "2") (pinfunction "E_2") (pintype "passive"))
      (node (ref "R10") (pin "1") (pinfunction "1_1") (pintype "passive"))
      (node (ref "U2") (pin "19") (pinfunction "RTS_19") (pintype "passive"))
    )
    (net (code "62") (name "/RXD") (class "Default")
      (node (ref "R3") (pin "2") (pinfunction "2_2") (pintype "passive"))
      (node (ref "U2") (pin "20") (pinfunction "RXD_20") (pintype "passive"))
    )
    (net (code "63") (name "/RXD2") (class "Default")
      (node (ref "A1") (pin "8") (pinfunction "TXD0/GPIO14_8") (pintype "bidirectional"))
      (node (ref "J1") (pin "3") (pinfunction "3_3") (pintype "passive"))
      (node (ref "Pi_Ext") (pin "8") (pinfunction "8_8") (pintype "passive"))
      (node (ref "U1") (pin "28") (pinfunction "SD2_28") (pintype "passive"))
    )
    (net (code "64") (name "/RXD3") (class "Default")
      (node (ref "QRScanner") (pin "4") (pinfunction "4_4") (pintype "passive"))
      (node (ref "U1") (pin "36") (pinfunction "IO23_36") (pintype "passive"))
    )
    (net (code "65") (name "/SCL") (class "Default")
      (node (ref "R2") (pin "2") (pinfunction "2_2") (pintype "passive"))
      (node (ref "Screen") (pin "3") (pinfunction "3_3") (pintype "passive"))
      (node (ref "U1") (pin "39") (pinfunction "IO22_39") (pintype "passive"))
    )
    (net (code "66") (name "/SDA") (class "Default")
      (node (ref "R1") (pin "2") (pinfunction "2_2") (pintype "passive"))
      (node (ref "Screen") (pin "4") (pinfunction "4_4") (pintype "passive"))
      (node (ref "U1") (pin "42") (pinfunction "IO21_42") (pintype "passive"))
    )
    (net (code "67") (name "/TXD") (class "Default")
      (node (ref "R4") (pin "2") (pinfunction "2_2") (pintype "passive"))
      (node (ref "U2") (pin "21") (pinfunction "TXD_21") (pintype "passive"))
    )
    (net (code "68") (name "/TXD2") (class "Default")
      (node (ref "A1") (pin "10") (pinfunction "RXD0/GPIO15_10") (pintype "bidirectional"))
      (node (ref "J1") (pin "4") (pinfunction "4_4") (pintype "passive"))
      (node (ref "Pi_Ext") (pin "10") (pinfunction "10_10") (pintype "passive"))
      (node (ref "U1") (pin "29") (pinfunction "SD3_29") (pintype "passive"))
    )
    (net (code "69") (name "/TXD3") (class "Default")
      (node (ref "QRScanner") (pin "3") (pinfunction "3_3") (pintype "passive"))
      (node (ref "U1") (pin "38") (pinfunction "IO19_38") (pintype "passive"))
    )
    (net (code "70") (name "/USB_DN") (class "Default")
      (node (ref "R12") (pin "1") (pinfunction "1_1") (pintype "passive"))
      (node (ref "U2") (pin "4") (pinfunction "D-_4") (pintype "passive"))
    )
    (net (code "71") (name "/USB_DP") (class "Default")
      (node (ref "R13") (pin "1") (pinfunction "1_1") (pintype "passive"))
      (node (ref "U2") (pin "3") (pinfunction "D+_3") (pintype "passive"))
    )
    (net (code "72") (name "GND") (class "Default")
      (node (ref "A1") (pin "6") (pinfunction "GND[8]_6") (pintype "power_in"))
      (node (ref "AE") (pin "1") (pinfunction "ANT_1") (pintype "passive"))
      (node (ref "AE") (pin "2") (pinfunction "2_2") (pintype "passive"))
      (node (ref "C1") (pin "2") (pinfunction "2_2") (pintype "passive"))
      (node (ref "C10") (pin "1") (pinfunction "1_1") (pintype "passive"))
      (node (ref "C11") (pin "2") (pinfunction "2_2") (pintype "passive"))
      (node (ref "C12") (pin "2") (pinfunction "2_2") (pintype "passive"))
      (node (ref "C2") (pin "1") (pinfunction "1_1") (pintype "passive"))
      (node (ref "C3") (pin "1") (pinfunction "1_1") (pintype "passive"))
      (node (ref "C4") (pin "1") (pinfunction "1_1") (pintype "passive"))
      (node (ref "C5") (pin "1") (pinfunction "1_1") (pintype "passive"))
      (node (ref "C6") (pin "1") (pinfunction "1_1") (pintype "passive"))
      (node (ref "C7") (pin "2") (pinfunction "2_2") (pintype "passive"))
      (node (ref "C8") (pin "2") (pinfunction "2_2") (pintype "passive"))
      (node (ref "C9") (pin "1") (pinfunction "1_1") (pintype "passive"))
      (node (ref "CR") (pin "1") (pinfunction "1_1") (pintype "passive"))
      (node (ref "D1") (pin "2") (pinfunction "2_2") (pintype "passive"))
      (node (ref "D2") (pin "2") (pinfunction "2_2") (pintype "passive"))
      (node (ref "GND") (pin "1") (pinfunction "1_1") (pintype "passive"))
      (node (ref "GND") (pin "2") (pinfunction "2_2") (pintype "passive"))
      (node (ref "J1") (pin "2") (pinfunction "2_2") (pintype "passive"))
      (node (ref "Jack") (pin "2") (pinfunction "2_2") (pintype "passive"))
      (node (ref "Jack") (pin "3") (pinfunction "3_3") (pintype "passive"))
      (node (ref "PWR_Lock") (pin "1") (pinfunction "1_1") (pintype "passive"))
      (node (ref "Pi_Ext") (pin "6") (pinfunction "6_6") (pintype "passive"))
      (node (ref "QRScanner") (pin "2") (pinfunction "2_2") (pintype "passive"))
      (node (ref "R6") (pin "2") (pinfunction "2_2") (pintype "passive"))
      (node (ref "R8") (pin "2") (pinfunction "2_2") (pintype "passive"))
      (node (ref "R9") (pin "2") (pinfunction "2_2") (pintype "passive"))
      (node (ref "RA") (pin "1") (pinfunction "1_1") (pintype "passive"))
      (node (ref "RV1") (pin "1") (pinfunction "1_1") (pintype "passive"))
      (node (ref "Relay") (pin "1") (pinfunction "1_1") (pintype "passive"))
      (node (ref "SW") (pin "1") (pinfunction "1_1") (pintype "passive"))
      (node (ref "Screen") (pin "2") (pinfunction "2_2") (pintype "passive"))
      (node (ref "U1") (pin "2") (pinfunction "LNA_IN_2") (pintype "passive"))
      (node (ref "U1") (pin "49") (pinfunction "GND_49") (pintype "passive"))
      (node (ref "U2") (pin "2") (pinfunction "GND_2") (pintype "passive"))
      (node (ref "U2") (pin "25") (pinfunction "GND_25") (pintype "passive"))
      (node (ref "U3") (pin "1") (pinfunction "GND_1") (pintype "passive"))
      (node (ref "U4") (pin "2") (pinfunction "GND_2") (pintype "passive"))
      (node (ref "U5") (pin "1") (pinfunction "GND_1") (pintype "passive"))
      (node (ref "USBC") (pin "0") (pinfunction "SH_0") (pintype "passive"))
      (node (ref "USBC") (pin "1") (pinfunction "SH_1") (pintype "passive"))
      (node (ref "USBC") (pin "2") (pinfunction "SH_2") (pintype "passive"))
      (node (ref "USBC") (pin "3") (pinfunction "SH_3") (pintype "passive"))
      (node (ref "USBC") (pin "A1") (pinfunction "GND_A1") (pintype "passive"))
      (node (ref "USBC") (pin "A12") (pinfunction "GND_A12") (pintype "passive"))
      (node (ref "USBC") (pin "B1") (pinfunction "GND_B1") (pintype "passive"))
      (node (ref "USBC") (pin "B12") (pinfunction "GND_B12") (pintype "passive"))
    )
    (net (code "73") (name "Net-(D3-K)") (class "Default")
      (node (ref "C9") (pin "2") (pinfunction "2_2") (pintype "passive"))
      (node (ref "D3") (pin "1") (pinfunction "K_1") (pintype "passive"))
      (node (ref "Q3") (pin "3") (pinfunction "S_3") (pintype "passive"))
      (node (ref "RV2") (pin "2") (pinfunction "2_2") (pintype "passive"))
      (node (ref "U4") (pin "1") (pinfunction "VIN_1") (pintype "passive"))
    )
    (net (code "74") (name "Net-(LEDA-Pad2)") (class "Default")
      (node (ref "LEDA") (pin "2") (pinfunction "2_2") (pintype "passive"))
      (node (ref "RA") (pin "2") (pinfunction "2_2") (pintype "passive"))
    )
    (net (code "75") (name "Net-(Q1-B)") (class "Default")
      (node (ref "Q1") (pin "1") (pinfunction "B_1") (pintype "passive"))
      (node (ref "R10") (pin "2") (pinfunction "2_2") (pintype "passive"))
    )
    (net (code "76") (name "Net-(Q2-B)") (class "Default")
      (node (ref "Q2") (pin "1") (pinfunction "B_1") (pintype "passive"))
      (node (ref "R11") (pin "2") (pinfunction "2_2") (pintype "passive"))
    )
    (net (code "77") (name "Net-(U2-RSTb)") (class "Default")
      (node (ref "R7") (pin "1") (pinfunction "1_1") (pintype "passive"))
      (node (ref "U2") (pin "9") (pinfunction "RSTb_9") (pintype "passive"))
    )
    (net (code "78") (name "Net-(U2-VBUS)") (class "Default")
      (node (ref "R5") (pin "2") (pinfunction "2_2") (pintype "passive"))
      (node (ref "R6") (pin "1") (pinfunction "1_1") (pintype "passive"))
      (node (ref "U2") (pin "8") (pinfunction "VBUS_8") (pintype "passive"))
    )
    (net (code "79") (name "Net-(U4-EN)") (class "Default")
      (node (ref "RV2") (pin "1") (pinfunction "1_1") (pintype "passive"))
      (node (ref "U4") (pin "3") (pinfunction "EN_3") (pintype "passive"))
    )
    (net (code "80") (name "Net-(USBC-CC1)") (class "Default")
      (node (ref "R9") (pin "1") (pinfunction "1_1") (pintype "passive"))
      (node (ref "USBC") (pin "A5") (pinfunction "CC1_A5") (pintype "passive"))
    )
    (net (code "81") (name "Net-(USBC-CC2)") (class "Default")
      (node (ref "R8") (pin "1") (pinfunction "1_1") (pintype "passive"))
      (node (ref "USBC") (pin "B5") (pinfunction "CC2_B5") (pintype "passive"))
    )
    (net (code "82") (name "VBUS") (class "Default")
      (node (ref "D3") (pin "2") (pinfunction "A_2") (pintype "passive"))
      (node (ref "Q3") (pin "1") (pinfunction "G_1") (pintype "passive"))
      (node (ref "R5") (pin "1") (pinfunction "1_1") (pintype "passive"))
      (node (ref "RV1") (pin "2") (pinfunction "2_2") (pintype "passive"))
      (node (ref "USBC") (pin "A4") (pinfunction "VBUS_A4") (pintype "passive"))
      (node (ref "USBC") (pin "A9") (pinfunction "VBUS_A9") (pintype "passive"))
      (node (ref "USBC") (pin "B4") (pinfunction "VBUS_B4") (pintype "passive"))
      (node (ref "USBC") (pin "B9") (pinfunction "VBUS_B9") (pintype "passive"))
    )
    (net (code "83") (name "unconnected-(U1-CAP1_NC-Pad48)") (class "Default")
      (node (ref "U1") (pin "48") (pinfunction "CAP1_NC_48") (pintype "passive+no_connect"))
    )
    (net (code "84") (name "unconnected-(U1-CAP2_NC-Pad47)") (class "Default")
      (node (ref "U1") (pin "47") (pinfunction "CAP2_NC_47") (pintype "passive+no_connect"))
    )
    (net (code "85") (name "unconnected-(U1-CLK-Pad31)") (class "Default")
      (node (ref "U1") (pin "31") (pinfunction "CLK_31") (pintype "passive+no_connect"))
    )
    (net (code "86") (name "unconnected-(U1-CMD-Pad30)") (class "Default")
      (node (ref "U1") (pin "30") (pinfunction "CMD_30") (pintype "passive+no_connect"))
    )
    (net (code "87") (name "unconnected-(U1-IO12-Pad18)") (class "Default")
      (node (ref "U1") (pin "18") (pinfunction "IO12_18") (pintype "passive+no_connect"))
    )
    (net (code "88") (name "unconnected-(U1-IO16-Pad25)") (class "Default")
      (node (ref "U1") (pin "25") (pinfunction "IO16_25") (pintype "passive+no_connect"))
    )
    (net (code "89") (name "unconnected-(U1-IO17-Pad27)") (class "Default")
      (node (ref "U1") (pin "27") (pinfunction "IO17_27") (pintype "passive+no_connect"))
    )
    (net (code "90") (name "unconnected-(U1-SD0-Pad32)") (class "Default")
      (node (ref "U1") (pin "32") (pinfunction "SD0_32") (pintype "passive+no_connect"))
    )
    (net (code "91") (name "unconnected-(U1-SD1-Pad33)") (class "Default")
      (node (ref "U1") (pin "33") (pinfunction "SD1_33") (pintype "passive+no_connect"))
    )
    (net (code "92") (name "unconnected-(U1-SENSOR_CAPN-Pad7)") (class "Default")
      (node (ref "U1") (pin "7") (pinfunction "SENSOR_CAPN_7") (pintype "passive+no_connect"))
    )
    (net (code "93") (name "unconnected-(U1-SENSOR_CAPP-Pad6)") (class "Default")
      (node (ref "U1") (pin "6") (pinfunction "SENSOR_CAPP_6") (pintype "passive+no_connect"))
    )
    (net (code "94") (name "unconnected-(U1-SENSOR_VN-Pad8)") (class "Default")
      (node (ref "U1") (pin "8") (pinfunction "SENSOR_VN_8") (pintype "passive+no_connect"))
    )
    (net (code "95") (name "unconnected-(U1-SENSOR_VP-Pad5)") (class "Default")
      (node (ref "U1") (pin "5") (pinfunction "SENSOR_VP_5") (pintype "passive+no_connect"))
    )
    (net (code "96") (name "unconnected-(U1-VDD_SDIO-Pad26)") (class "Default")
      (node (ref "U1") (pin "26") (pinfunction "VDD_SDIO_26") (pintype "passive+no_connect"))
    )
    (net (code "97") (name "unconnected-(U1-XTAL_N_NC-Pad44)") (class "Default")
      (node (ref "U1") (pin "44") (pinfunction "XTAL_N_NC_44") (pintype "passive+no_connect"))
    )
    (net (code "98") (name "unconnected-(U1-XTAL_P_NC-Pad45)") (class "Default")
      (node (ref "U1") (pin "45") (pinfunction "XTAL_P_NC_45") (pintype "passive+no_connect"))
    )
    (net (code "99") (name "unconnected-(U2-CTS-Pad18)") (class "Default")
      (node (ref "U2") (pin "18") (pinfunction "CTS_18") (pintype "passive+no_connect"))
    )
    (net (code "100") (name "unconnected-(U2-DCD-Pad24)") (class "Default")
      (node (ref "U2") (pin "24") (pinfunction "DCD_24") (pintype "passive+no_connect"))
    )
    (net (code "101") (name "unconnected-(U2-DSR-Pad22)") (class "Default")
      (node (ref "U2") (pin "22") (pinfunction "DSR_22") (pintype "passive+no_connect"))
    )
    (net (code "102") (name "unconnected-(U2-GPIO.0{slash}TXT-Pad14)") (class "Default")
      (node (ref "U2") (pin "14") (pinfunction "GPIO.0/TXT_14") (pintype "passive+no_connect"))
    )
    (net (code "103") (name "unconnected-(U2-GPIO.1{slash}RXT-Pad13)") (class "Default")
      (node (ref "U2") (pin "13") (pinfunction "GPIO.1/RXT_13") (pintype "passive+no_connect"))
    )
    (net (code "104") (name "unconnected-(U2-GPIO.2{slash}RS485-Pad12)") (class "Default")
      (node (ref "U2") (pin "12") (pinfunction "GPIO.2/RS485_12") (pintype "passive+no_connect"))
    )
    (net (code "105") (name "unconnected-(U2-GPIO.3{slash}WAKEUP-Pad11)") (class "Default")
      (node (ref "U2") (pin "11") (pinfunction "GPIO.3/WAKEUP_11") (pintype "passive+no_connect"))
    )
    (net (code "106") (name "unconnected-(U2-NC-Pad10)") (class "Default")
      (node (ref "U2") (pin "10") (pinfunction "NC_10") (pintype "passive+no_connect"))
    )
    (net (code "107") (name "unconnected-(U2-NC-Pad16)") (class "Default")
      (node (ref "U2") (pin "16") (pinfunction "NC_16") (pintype "passive+no_connect"))
    )
    (net (code "108") (name "unconnected-(U2-RI{slash}CLK-Pad1)") (class "Default")
      (node (ref "U2") (pin "1") (pinfunction "RI/CLK_1") (pintype "passive+no_connect"))
    )
    (net (code "109") (name "unconnected-(U2-SUSPEND-Pad17)") (class "Default")
      (node (ref "U2") (pin "17") (pinfunction "SUSPEND_17") (pintype "passive+no_connect"))
    )
    (net (code "110") (name "unconnected-(U2-SUSPENDb-Pad15)") (class "Default")
      (node (ref "U2") (pin "15") (pinfunction "SUSPENDb_15") (pintype "passive+no_connect"))
    )
    (net (code "111") (name "unconnected-(U4-NC-Pad4)") (class "Default")
      (node (ref "U4") (pin "4") (pinfunction "NC_4") (pintype "passive+no_connect"))
    )
    (net (code "112") (name "unconnected-(USBC-SBU1-PadA8)") (class "Default")
      (node (ref "USBC") (pin "A8") (pinfunction "SBU1_A8") (pintype "passive+no_connect"))
    )
    (net (code "113") (name "unconnected-(USBC-SBU2-PadB8)") (class "Default")
      (node (ref "USBC") (pin "B8") (pinfunction "SBU2_B8") (pintype "passive+no_connect"))
    )
  )
)
